# 07_WIFI.net
KiCad netlist of a schematic drawn in Altium Designer
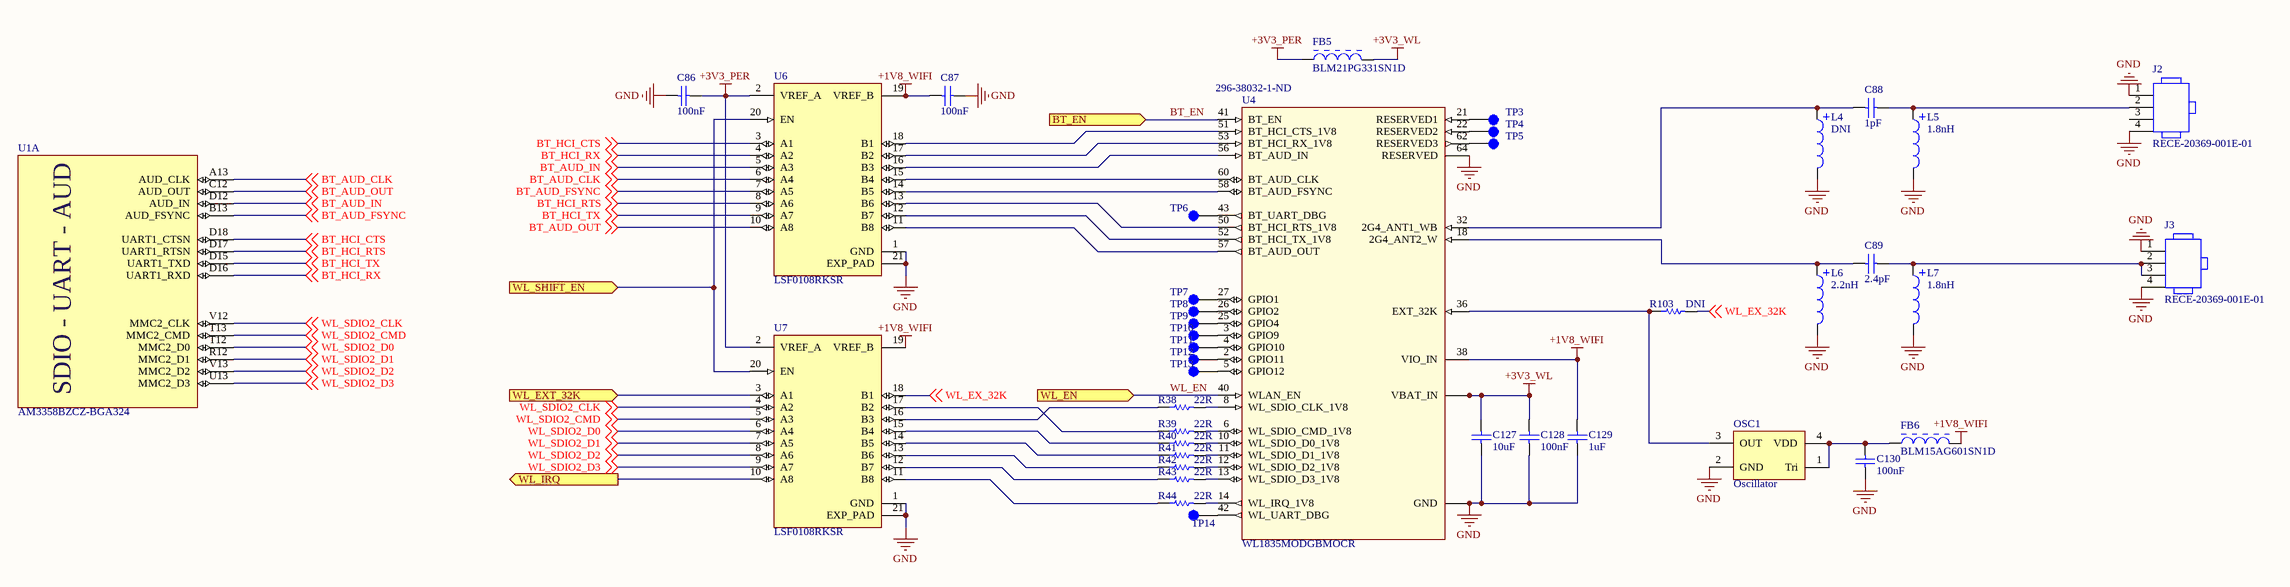
[diagram p0: 07. WIFI.SchDoc]

(export (version "E")
  (design (tool "Eeschema 10.0.6"))
  (components
    (comp (ref "C86")
      (value "100nF")
      (footprint "CAPC1005X60X30LL05T10")
      (description "Chip Capacitor, 0.1 uF, +/- 10%, 16 V, -55 to 125 degC, 0402 (1005 Metric), RoHS, Tape and Reel")
      (fields (field (name "VOLTAGE") "16V") (field (name "TOLERANCE") "10%"))
      (libsource (lib "AM3358_DEV_BOARD") (part "CAP-NP-2"))
    )
    (comp (ref "C87")
      (value "100nF")
      (footprint "CAPC1005X60X30LL05T10")
      (description "Chip Capacitor, 0.1 uF, +/- 10%, 16 V, -55 to 125 degC, 0402 (1005 Metric), RoHS, Tape and Reel")
      (fields (field (name "VOLTAGE") "16V") (field (name "TOLERANCE") "10%"))
      (libsource (lib "AM3358_DEV_BOARD") (part "CAP-NP-2"))
    )
    (comp (ref "C88")
      (value "1pF")
      (footprint "CAPC1005X60X30LL05T10")
      (description "Ceramic; Cap 1 pF; Tol 0.25 pF; Vol-Rtg 50 VDC; SMT; 0402; C0G; Tape & Reel")
      (fields
        (field (name "PART NUMBER") "04025A1R0CAT2A")
        (field (name "MANUFACTURER") "AVX Interconnect / Elco")
      )
      (libsource (lib "AM3358_DEV_BOARD") (part "CAP"))
    )
    (comp (ref "C89")
      (value "2.4pF")
      (footprint "CAPC1005X60X30LL05T10")
      (description "CAP 2.4pF 16V ±0.25pF 01005 (0402 Metric) Thickness 0.22mm SMD")
      (fields (field (name "TOLERANCE") "Â±0.25pF"))
      (libsource (lib "AM3358_DEV_BOARD") (part "CAP"))
    )
    (comp (ref "C127")
      (value "10uF")
      (footprint "CAPC1608X90X35ML10T15")
      (description "Chip Capacitor, 10 uF, +/- 10%, 6.3 V, -55 to 125 degC, 0603 (1608 Metric), RoHS, Tape and Reel")
      (fields (field (name "PART NUMBER") "GRM188R60J106ME47D") (field (name "MANUFACTURER") "Murata"))
      (libsource (lib "Altium Content Vault") (part "CAP"))
    )
    (comp (ref "C128")
      (value "100nF")
      (footprint "CAPC1005X60X30LL05T10")
      (description "Chip Capacitor, 0.1 uF, +/- 10%, 16 V, -55 to 125 degC, 0402 (1005 Metric), RoHS, Tape and Reel")
      (fields (field (name "VOLTAGE") "16V") (field (name "TOLERANCE") "10%"))
      (libsource (lib "AM3358_DEV_BOARD") (part "CAP-NP-2"))
    )
    (comp (ref "C129")
      (value "1uF")
      (footprint "CAPC0402(1005)60_M")
      (description "CAP 1uF 6.3V ±10% 0402 (1005 Metric) Thickness 0.6mm SMD")
      (fields (field (name "TOLERANCE") "Â±10%"))
      (libsource (lib "Altium Content Vault") (part "CAP"))
    )
    (comp (ref "C130")
      (value "100nF")
      (footprint "CAPC1005X60X30LL05T10")
      (description "Chip Capacitor, 0.1 uF, +/- 10%, 16 V, -55 to 125 degC, 0402 (1005 Metric), RoHS, Tape and Reel")
      (fields (field (name "VOLTAGE") "16V") (field (name "TOLERANCE") "10%"))
      (libsource (lib "AM3358_DEV_BOARD") (part "CAP-NP-2"))
    )
    (comp (ref "FB5")
      (value "BLM21PG331SN1D")
      (footprint "MURA-BLM21-H1-CHIP-2_V")
      (fields (field (name "MANUFACTURER") "Murata"))
      (libsource (lib "Altium Content Vault") (part "MURA-FB-2"))
    )
    (comp (ref "FB6")
      (value "BLM15AG601SN1D")
      (footprint "MURA-BLM15-CHIP-2_V")
      (fields (field (name "MANUFACTURER") "Murata"))
      (libsource (lib "Altium Content Vault") (part "MURA-FB-2"))
    )
    (comp (ref "J2")
      (value "RECE-20369-001E-01")
      (footprint "TG-RECE-20369-001E-4_V")
      (description "RF Connector, Onboard Receptacle, IPEX MHFIII")
      (fields (field (name "MANUFACTURER") "Taoglas"))
      (libsource (lib "Altium Content Vault") (part "TG-RECE-20369-001E-01-4"))
    )
    (comp (ref "J3")
      (value "RECE-20369-001E-01")
      (footprint "TG-RECE-20369-001E-4_V")
      (description "RF Connector, Onboard Receptacle, IPEX MHFIII")
      (fields (field (name "MANUFACTURER") "Taoglas"))
      (libsource (lib "Altium Content Vault") (part "TG-RECE-20369-001E-01-4"))
    )
    (comp (ref "L4")
      (value "DNI")
      (footprint "INDC1005X55X25ML5T10")
      (fields (field (name "TOLERANCE") "1%"))
      (libsource (lib "Altium Content Vault") (part "IND_POLAR-2"))
    )
    (comp (ref "L5")
      (value "1.8nH")
      (footprint "INDC1005X55X25ML5T10")
      (fields (field (name "TOLERANCE") "1%"))
      (libsource (lib "Altium Content Vault") (part "IND_POLAR-2"))
    )
    (comp (ref "L6")
      (value "2.2nH")
      (footprint "INDC1005X55X25ML5T10")
      (fields (field (name "TOLERANCE") "1%"))
      (libsource (lib "Altium Content Vault") (part "IND_POLAR-2"))
    )
    (comp (ref "L7")
      (value "1.8nH")
      (footprint "INDC1005X55X25ML5T10")
      (fields (field (name "TOLERANCE") "1%"))
      (libsource (lib "Altium Content Vault") (part "IND_POLAR-2"))
    )
    (comp (ref "OSC1")
      (value "Oscillator")
      (footprint "FP-NX3225SA-MFG")
      (libsource (lib "SyTungNguyen") (part "Oscillator"))
    )
    (comp (ref "R38")
      (value "22R")
      (footprint "RESC1005X40X25LL05T05")
      (description "Chip Resistor, 22 Ohm, +/- 1%, 0.1 W, -55 to 155 degC, 0402 (1005 Metric), RoHS, Tape and Reel")
      (fields (field (name "PARTNUMBER") "ERJ-2RKF22R0X") (field (name "TOLERANCE") "1%"))
      (libsource (lib "AM3358_DEV_BOARD") (part "RES-2"))
    )
    (comp (ref "R39")
      (value "22R")
      (footprint "RESC1005X40X25LL05T05")
      (description "Chip Resistor, 22 Ohm, +/- 1%, 0.1 W, -55 to 155 degC, 0402 (1005 Metric), RoHS, Tape and Reel")
      (fields (field (name "PARTNUMBER") "ERJ-2RKF22R0X") (field (name "TOLERANCE") "1%"))
      (libsource (lib "AM3358_DEV_BOARD") (part "RES-2"))
    )
    (comp (ref "R40")
      (value "22R")
      (footprint "RESC1005X40X25LL05T05")
      (description "Chip Resistor, 22 Ohm, +/- 1%, 0.1 W, -55 to 155 degC, 0402 (1005 Metric), RoHS, Tape and Reel")
      (fields (field (name "PARTNUMBER") "ERJ-2RKF22R0X") (field (name "TOLERANCE") "1%"))
      (libsource (lib "AM3358_DEV_BOARD") (part "RES-2"))
    )
    (comp (ref "R41")
      (value "22R")
      (footprint "RESC1005X40X25LL05T05")
      (description "Chip Resistor, 22 Ohm, +/- 1%, 0.1 W, -55 to 155 degC, 0402 (1005 Metric), RoHS, Tape and Reel")
      (fields (field (name "PARTNUMBER") "ERJ-2RKF22R0X") (field (name "TOLERANCE") "1%"))
      (libsource (lib "AM3358_DEV_BOARD") (part "RES-2"))
    )
    (comp (ref "R42")
      (value "22R")
      (footprint "RESC1005X40X25LL05T05")
      (description "Chip Resistor, 22 Ohm, +/- 1%, 0.1 W, -55 to 155 degC, 0402 (1005 Metric), RoHS, Tape and Reel")
      (fields (field (name "PARTNUMBER") "ERJ-2RKF22R0X") (field (name "TOLERANCE") "1%"))
      (libsource (lib "AM3358_DEV_BOARD") (part "RES-2"))
    )
    (comp (ref "R43")
      (value "22R")
      (footprint "RESC1005X40X25LL05T05")
      (description "Chip Resistor, 22 Ohm, +/- 1%, 0.1 W, -55 to 155 degC, 0402 (1005 Metric), RoHS, Tape and Reel")
      (fields (field (name "PARTNUMBER") "ERJ-2RKF22R0X") (field (name "TOLERANCE") "1%"))
      (libsource (lib "AM3358_DEV_BOARD") (part "RES-2"))
    )
    (comp (ref "R44")
      (value "22R")
      (footprint "RESC1005X40X25LL05T05")
      (description "Chip Resistor, 22 Ohm, +/- 1%, 0.1 W, -55 to 155 degC, 0402 (1005 Metric), RoHS, Tape and Reel")
      (fields (field (name "PARTNUMBER") "ERJ-2RKF22R0X") (field (name "TOLERANCE") "1%"))
      (libsource (lib "AM3358_DEV_BOARD") (part "RES-2"))
    )
    (comp (ref "R103")
      (value "DNI")
      (footprint "RESC1005X40X25LL05T05")
      (description "Chip Resistor, 22 Ohm, +/- 1%, 0.1 W, -55 to 155 degC, 0402 (1005 Metric), RoHS, Tape and Reel")
      (fields (field (name "PARTNUMBER") "ERJ-2RKF22R0X") (field (name "TOLERANCE") "1%"))
      (libsource (lib "AM3358_DEV_BOARD") (part "RES-2"))
    )
    (comp (ref "TP3") (value "Test Point") (footprint "TP") (libsource (lib "SyTungNguyen") (part "TP")))
    (comp (ref "TP4") (value "Test Point") (footprint "TP") (libsource (lib "SyTungNguyen") (part "TP")))
    (comp (ref "TP5") (value "Test Point") (footprint "TP") (libsource (lib "SyTungNguyen") (part "TP")))
    (comp (ref "TP6") (value "Test Point") (footprint "TP") (libsource (lib "SyTungNguyen") (part "TP")))
    (comp (ref "TP7") (value "Test Point") (footprint "TP") (libsource (lib "SyTungNguyen") (part "TP")))
    (comp (ref "TP8") (value "Test Point") (footprint "TP") (libsource (lib "SyTungNguyen") (part "TP")))
    (comp (ref "TP9") (value "Test Point") (footprint "TP") (libsource (lib "SyTungNguyen") (part "TP")))
    (comp (ref "TP10") (value "Test Point") (footprint "TP") (libsource (lib "SyTungNguyen") (part "TP")))
    (comp (ref "TP11") (value "Test Point") (footprint "TP") (libsource (lib "SyTungNguyen") (part "TP")))
    (comp (ref "TP12") (value "Test Point") (footprint "TP") (libsource (lib "SyTungNguyen") (part "TP")))
    (comp (ref "TP13") (value "Test Point") (footprint "TP") (libsource (lib "SyTungNguyen") (part "TP")))
    (comp (ref "TP14") (value "Test Point") (footprint "TP") (libsource (lib "SyTungNguyen") (part "TP")))
    (comp (ref "U1")
      (value "AM3358BZCZ-BGA324")
      (footprint "TI-ZCZ324")
      (libsource (lib "SyTungNguyen") (part "AM3358BZCZ100"))
    )
    (comp (ref "U4")
      (value "WL1835MODGBMOCR")
      (footprint "WL1835MODGBMOCR")
      (description "Bluetooth, WiFi 802.11b/g/n, Bluetooth 4.2 Transceiver Module 2.4GHz Surface Mount")
      (fields (field (name "SUPPLIER PART NUMBER 1") "296-38032-1-ND"))
      (libsource (lib "AM3358_DEV_BOARD") (part "WL1835MOD"))
    )
    (comp (ref "U6")
      (value "LSF0108RKSR")
      (footprint "QFN50P450X250X100-21N")
      (description "Voltage Level Translator Bidirectional 1 Circuit 8 Channel 20-VQFN _4.5x2.5_")
      (fields (field (name "MF") "Texas Instruments"))
      (libsource (lib "SyTungNguyen") (part "LSF0108"))
    )
    (comp (ref "U7")
      (value "LSF0108RKSR")
      (footprint "QFN50P450X250X100-21N")
      (description "Voltage Level Translator Bidirectional 1 Circuit 8 Channel 20-VQFN _4.5x2.5_")
      (fields (field (name "MF") "Texas Instruments"))
      (libsource (lib "SyTungNguyen") (part "LSF0108"))
    )
  )
  (nets
    (net (code "1") (name "+1V8_WIFI") (class "Default")
      (node (ref "C129") (pin "1") (pinfunction "1_1") (pintype "passive"))
      (node (ref "C87") (pin "2") (pinfunction "2_2") (pintype "passive"))
      (node (ref "FB6") (pin "2") (pinfunction "2_2") (pintype "passive"))
      (node (ref "U4") (pin "38") (pinfunction "VIO_IN_38") (pintype "power_in"))
      (node (ref "U6") (pin "19") (pinfunction "VREF_B_19") (pintype "power_in"))
      (node (ref "U7") (pin "19") (pinfunction "VREF_B_19") (pintype "power_in"))
    )
    (net (code "2") (name "+3V3_PER") (class "Default")
      (node (ref "C86") (pin "2") (pinfunction "2_2") (pintype "passive"))
      (node (ref "FB5") (pin "1") (pinfunction "1_1") (pintype "passive"))
      (node (ref "U6") (pin "2") (pinfunction "VREF_A_2") (pintype "power_in"))
      (node (ref "U7") (pin "2") (pinfunction "VREF_A_2") (pintype "power_in"))
    )
    (net (code "3") (name "+3V3_WL") (class "Default")
      (node (ref "C127") (pin "2") (pinfunction "2_2") (pintype "passive"))
      (node (ref "C128") (pin "2") (pinfunction "2_2") (pintype "passive"))
      (node (ref "FB5") (pin "2") (pinfunction "2_2") (pintype "passive"))
      (node (ref "U4") (pin "46") (pinfunction "VBAT_IN_46") (pintype "power_in"))
      (node (ref "U4") (pin "47") (pinfunction "VBAT_IN_47") (pintype "power_in"))
    )
    (net (code "4") (name "/BT_EN") (class "Default")
      (node (ref "U4") (pin "41") (pinfunction "BT_EN_41") (pintype "input"))
    )
    (net (code "5") (name "/WL_EN") (class "Default")
      (node (ref "U4") (pin "40") (pinfunction "WLAN_EN_40") (pintype "input"))
    )
    (net (code "6") (name "/WL_EXT_32K") (class "Default")
      (node (ref "U7") (pin "3") (pinfunction "A1_3") (pintype "bidirectional"))
    )
    (net (code "7") (name "/WL_IRQ") (class "Default")
      (node (ref "U7") (pin "10") (pinfunction "A8_10") (pintype "bidirectional"))
    )
    (net (code "8") (name "/WL_SHIFT_EN") (class "Default")
      (node (ref "U6") (pin "20") (pinfunction "EN_20") (pintype "input"))
      (node (ref "U7") (pin "20") (pinfunction "EN_20") (pintype "input"))
    )
    (net (code "9") (name "BT_AUD_CLK") (class "Default")
      (node (ref "U1") (pin "A13") (pinfunction "AUD_CLK_A13") (pintype "bidirectional"))
      (node (ref "U6") (pin "6") (pinfunction "A4_6") (pintype "bidirectional"))
    )
    (net (code "10") (name "BT_AUD_FSYNC") (class "Default")
      (node (ref "U1") (pin "B13") (pinfunction "AUD_FSYNC_B13") (pintype "bidirectional"))
      (node (ref "U6") (pin "7") (pinfunction "A5_7") (pintype "bidirectional"))
    )
    (net (code "11") (name "BT_AUD_IN") (class "Default")
      (node (ref "U1") (pin "D12") (pinfunction "AUD_IN_D12") (pintype "bidirectional"))
      (node (ref "U6") (pin "5") (pinfunction "A3_5") (pintype "bidirectional"))
    )
    (net (code "12") (name "BT_AUD_OUT") (class "Default")
      (node (ref "U1") (pin "C12") (pinfunction "AUD_OUT_C12") (pintype "bidirectional"))
      (node (ref "U6") (pin "10") (pinfunction "A8_10") (pintype "bidirectional"))
    )
    (net (code "13") (name "BT_HCI_CTS") (class "Default")
      (node (ref "U1") (pin "D18") (pinfunction "UART1_CTSN_D18") (pintype "bidirectional"))
      (node (ref "U6") (pin "3") (pinfunction "A1_3") (pintype "bidirectional"))
    )
    (net (code "14") (name "BT_HCI_RTS") (class "Default")
      (node (ref "U1") (pin "D17") (pinfunction "UART1_RTSN_D17") (pintype "bidirectional"))
      (node (ref "U6") (pin "8") (pinfunction "A6_8") (pintype "bidirectional"))
    )
    (net (code "15") (name "BT_HCI_RX") (class "Default")
      (node (ref "U1") (pin "D16") (pinfunction "UART1_RXD_D16") (pintype "bidirectional"))
      (node (ref "U6") (pin "4") (pinfunction "A2_4") (pintype "bidirectional"))
    )
    (net (code "16") (name "BT_HCI_TX") (class "Default")
      (node (ref "U1") (pin "D15") (pinfunction "UART1_TXD_D15") (pintype "bidirectional"))
      (node (ref "U6") (pin "9") (pinfunction "A7_9") (pintype "bidirectional"))
    )
    (net (code "17") (name "GND") (class "Default")
      (node (ref "C127") (pin "1") (pinfunction "1_1") (pintype "passive"))
      (node (ref "C128") (pin "1") (pinfunction "1_1") (pintype "passive"))
      (node (ref "C129") (pin "2") (pinfunction "2_2") (pintype "passive"))
      (node (ref "C130") (pin "1") (pinfunction "1_1") (pintype "passive"))
      (node (ref "C86") (pin "1") (pinfunction "1_1") (pintype "passive"))
      (node (ref "C87") (pin "1") (pinfunction "1_1") (pintype "passive"))
      (node (ref "J2") (pin "1") (pinfunction "1_1") (pintype "passive"))
      (node (ref "J2") (pin "4") (pinfunction "4_4") (pintype "passive"))
      (node (ref "J3") (pin "1") (pinfunction "1_1") (pintype "passive"))
      (node (ref "J3") (pin "4") (pinfunction "4_4") (pintype "passive"))
      (node (ref "L4") (pin "2") (pinfunction "2_2") (pintype "passive"))
      (node (ref "L5") (pin "2") (pinfunction "2_2") (pintype "passive"))
      (node (ref "L6") (pin "2") (pinfunction "2_2") (pintype "passive"))
      (node (ref "L7") (pin "2") (pinfunction "2_2") (pintype "passive"))
      (node (ref "OSC1") (pin "2") (pinfunction "GND_2") (pintype "passive"))
      (node (ref "U4") (pin "1") (pinfunction "GND_1") (pintype "passive"))
      (node (ref "U4") (pin "15") (pinfunction "GND_15") (pintype "passive"))
      (node (ref "U4") (pin "16") (pinfunction "GND_16") (pintype "passive"))
      (node (ref "U4") (pin "17") (pinfunction "GND_17") (pintype "passive"))
      (node (ref "U4") (pin "19") (pinfunction "GND_19") (pintype "passive"))
      (node (ref "U4") (pin "20") (pinfunction "GND_20") (pintype "passive"))
      (node (ref "U4") (pin "23") (pinfunction "GND_23") (pintype "passive"))
      (node (ref "U4") (pin "24") (pinfunction "GND_24") (pintype "passive"))
      (node (ref "U4") (pin "28") (pinfunction "GND_28") (pintype "passive"))
      (node (ref "U4") (pin "29") (pinfunction "GND_29") (pintype "passive"))
      (node (ref "U4") (pin "30") (pinfunction "GND_30") (pintype "passive"))
      (node (ref "U4") (pin "31") (pinfunction "GND_31") (pintype "passive"))
      (node (ref "U4") (pin "33") (pinfunction "GND_33") (pintype "passive"))
      (node (ref "U4") (pin "34") (pinfunction "GND_34") (pintype "passive"))
      (node (ref "U4") (pin "35") (pinfunction "GND_35") (pintype "passive"))
      (node (ref "U4") (pin "37") (pinfunction "GND_37") (pintype "passive"))
      (node (ref "U4") (pin "39") (pinfunction "GND_39") (pintype "passive"))
      (node (ref "U4") (pin "44") (pinfunction "GND_44") (pintype "passive"))
      (node (ref "U4") (pin "45") (pinfunction "GND_45") (pintype "passive"))
      (node (ref "U4") (pin "48") (pinfunction "GND_48") (pintype "passive"))
      (node (ref "U4") (pin "49") (pinfunction "GND_49") (pintype "passive"))
      (node (ref "U4") (pin "54") (pinfunction "GND_54") (pintype "passive"))
      (node (ref "U4") (pin "55") (pinfunction "GND_55") (pintype "passive"))
      (node (ref "U4") (pin "59") (pinfunction "GND_59") (pintype "passive"))
      (node (ref "U4") (pin "61") (pinfunction "GND_61") (pintype "passive"))
      (node (ref "U4") (pin "63") (pinfunction "GND_63") (pintype "passive"))
      (node (ref "U4") (pin "64") (pinfunction "RESERVED_64") (pintype "passive"))
      (node (ref "U4") (pin "7") (pinfunction "GND_7") (pintype "passive"))
      (node (ref "U4") (pin "9") (pinfunction "GND_9") (pintype "passive"))
      (node (ref "U4") (pin "G1") (pinfunction "GND_G1") (pintype "passive"))
      (node (ref "U4") (pin "G10") (pinfunction "GND_G10") (pintype "passive"))
      (node (ref "U4") (pin "G11") (pinfunction "GND_G11") (pintype "passive"))
      (node (ref "U4") (pin "G12") (pinfunction "GND_G12") (pintype "passive"))
      (node (ref "U4") (pin "G13") (pinfunction "GND_G13") (pintype "passive"))
      (node (ref "U4") (pin "G14") (pinfunction "GND_G14") (pintype "passive"))
      (node (ref "U4") (pin "G15") (pinfunction "GND_G15") (pintype "passive"))
      (node (ref "U4") (pin "G16") (pinfunction "GND_G16") (pintype "passive"))
      (node (ref "U4") (pin "G17") (pinfunction "GND_G17") (pintype "passive"))
      (node (ref "U4") (pin "G18") (pinfunction "GND_G18") (pintype "passive"))
      (node (ref "U4") (pin "G19") (pinfunction "GND_G19") (pintype "passive"))
      (node (ref "U4") (pin "G2") (pinfunction "GND_G2") (pintype "passive"))
      (node (ref "U4") (pin "G20") (pinfunction "GND_G20") (pintype "passive"))
      (node (ref "U4") (pin "G21") (pinfunction "GND_G21") (pintype "passive"))
      (node (ref "U4") (pin "G22") (pinfunction "GND_G22") (pintype "passive"))
      (node (ref "U4") (pin "G23") (pinfunction "GND_G23") (pintype "passive"))
      (node (ref "U4") (pin "G24") (pinfunction "GND_G24") (pintype "passive"))
      (node (ref "U4") (pin "G25") (pinfunction "GND_G25") (pintype "passive"))
      (node (ref "U4") (pin "G26") (pinfunction "GND_G26") (pintype "passive"))
      (node (ref "U4") (pin "G27") (pinfunction "GND_G27") (pintype "passive"))
      (node (ref "U4") (pin "G28") (pinfunction "GND_G28") (pintype "passive"))
      (node (ref "U4") (pin "G29") (pinfunction "GND_G29") (pintype "passive"))
      (node (ref "U4") (pin "G3") (pinfunction "GND_G3") (pintype "passive"))
      (node (ref "U4") (pin "G30") (pinfunction "GND_G30") (pintype "passive"))
      (node (ref "U4") (pin "G31") (pinfunction "GND_G31") (pintype "passive"))
      (node (ref "U4") (pin "G32") (pinfunction "GND_G32") (pintype "passive"))
      (node (ref "U4") (pin "G33") (pinfunction "GND_G33") (pintype "passive"))
      (node (ref "U4") (pin "G34") (pinfunction "GND_G34") (pintype "passive"))
      (node (ref "U4") (pin "G35") (pinfunction "GND_G35") (pintype "passive"))
      (node (ref "U4") (pin "G36") (pinfunction "GND_G36") (pintype "passive"))
      (node (ref "U4") (pin "G4") (pinfunction "GND_G4") (pintype "passive"))
      (node (ref "U4") (pin "G5") (pinfunction "GND_G5") (pintype "passive"))
      (node (ref "U4") (pin "G6") (pinfunction "GND_G6") (pintype "passive"))
      (node (ref "U4") (pin "G7") (pinfunction "GND_G7") (pintype "passive"))
      (node (ref "U4") (pin "G8") (pinfunction "GND_G8") (pintype "passive"))
      (node (ref "U4") (pin "G9") (pinfunction "GND_G9") (pintype "passive"))
      (node (ref "U6") (pin "1") (pinfunction "GND_1") (pintype "power_in"))
      (node (ref "U6") (pin "21") (pinfunction "EXP_PAD_21") (pintype "power_in"))
      (node (ref "U7") (pin "1") (pinfunction "GND_1") (pintype "power_in"))
      (node (ref "U7") (pin "21") (pinfunction "EXP_PAD_21") (pintype "power_in"))
    )
    (net (code "18") (name "Net-(C88-Pad2)") (class "Default")
      (node (ref "C88") (pin "2") (pinfunction "2_2") (pintype "passive"))
      (node (ref "J2") (pin "2") (pinfunction "2_2") (pintype "passive"))
      (node (ref "L5") (pin "1") (pinfunction "1_1") (pintype "passive"))
    )
    (net (code "19") (name "Net-(C89-Pad2)") (class "Default")
      (node (ref "C89") (pin "2") (pinfunction "2_2") (pintype "passive"))
      (node (ref "J3") (pin "2") (pinfunction "2_2") (pintype "passive"))
      (node (ref "J3") (pin "3") (pinfunction "3_3") (pintype "passive"))
      (node (ref "L7") (pin "1") (pinfunction "1_1") (pintype "passive"))
    )
    (net (code "20") (name "Net-(OSC1-OUT)") (class "Default")
      (node (ref "OSC1") (pin "3") (pinfunction "OUT_3") (pintype "passive"))
      (node (ref "R103") (pin "1") (pinfunction "1_1") (pintype "passive"))
      (node (ref "U4") (pin "36") (pinfunction "EXT_32K_36") (pintype "input"))
    )
    (net (code "21") (name "Net-(OSC1-Tri)") (class "Default")
      (node (ref "C130") (pin "2") (pinfunction "2_2") (pintype "passive"))
      (node (ref "FB6") (pin "1") (pinfunction "1_1") (pintype "passive"))
      (node (ref "OSC1") (pin "1") (pinfunction "Tri_1") (pintype "passive"))
      (node (ref "OSC1") (pin "4") (pinfunction "VDD_4") (pintype "passive"))
    )
    (net (code "22") (name "Net-(U4-2G4_ANT1_WB)") (class "Default")
      (node (ref "C88") (pin "1") (pinfunction "1_1") (pintype "passive"))
      (node (ref "L4") (pin "1") (pinfunction "1_1") (pintype "passive"))
      (node (ref "U4") (pin "32") (pinfunction "2G4_ANT1_WB_32") (pintype "input"))
    )
    (net (code "23") (name "Net-(U4-2G4_ANT2_W)") (class "Default")
      (node (ref "C89") (pin "1") (pinfunction "1_1") (pintype "passive"))
      (node (ref "L6") (pin "1") (pinfunction "1_1") (pintype "passive"))
      (node (ref "U4") (pin "18") (pinfunction "2G4_ANT2_W_18") (pintype "input"))
    )
    (net (code "24") (name "Net-(U4-BT_AUD_CLK)") (class "Default")
      (node (ref "U4") (pin "60") (pinfunction "BT_AUD_CLK_60") (pintype "bidirectional"))
      (node (ref "U6") (pin "15") (pinfunction "B4_15") (pintype "bidirectional"))
    )
    (net (code "25") (name "Net-(U4-BT_AUD_FSYNC)") (class "Default")
      (node (ref "U4") (pin "58") (pinfunction "BT_AUD_FSYNC_58") (pintype "bidirectional"))
      (node (ref "U6") (pin "14") (pinfunction "B5_14") (pintype "bidirectional"))
    )
    (net (code "26") (name "Net-(U4-BT_AUD_IN)") (class "Default")
      (node (ref "U4") (pin "56") (pinfunction "BT_AUD_IN_56") (pintype "input"))
      (node (ref "U6") (pin "16") (pinfunction "B3_16") (pintype "bidirectional"))
    )
    (net (code "27") (name "Net-(U4-BT_AUD_OUT)") (class "Default")
      (node (ref "U4") (pin "57") (pinfunction "BT_AUD_OUT_57") (pintype "output"))
      (node (ref "U6") (pin "11") (pinfunction "B8_11") (pintype "bidirectional"))
    )
    (net (code "28") (name "Net-(U4-BT_HCI_CTS_1V8)") (class "Default")
      (node (ref "U4") (pin "51") (pinfunction "BT_HCI_CTS_1V8_51") (pintype "input"))
      (node (ref "U6") (pin "18") (pinfunction "B1_18") (pintype "bidirectional"))
    )
    (net (code "29") (name "Net-(U4-BT_HCI_RTS_1V8)") (class "Default")
      (node (ref "U4") (pin "50") (pinfunction "BT_HCI_RTS_1V8_50") (pintype "output"))
      (node (ref "U6") (pin "13") (pinfunction "B6_13") (pintype "bidirectional"))
    )
    (net (code "30") (name "Net-(U4-BT_HCI_RX_1V8)") (class "Default")
      (node (ref "U4") (pin "53") (pinfunction "BT_HCI_RX_1V8_53") (pintype "input"))
      (node (ref "U6") (pin "17") (pinfunction "B2_17") (pintype "bidirectional"))
    )
    (net (code "31") (name "Net-(U4-BT_HCI_TX_1V8)") (class "Default")
      (node (ref "U4") (pin "52") (pinfunction "BT_HCI_TX_1V8_52") (pintype "output"))
      (node (ref "U6") (pin "12") (pinfunction "B7_12") (pintype "bidirectional"))
    )
    (net (code "32") (name "Net-(U4-BT_UART_DBG)") (class "Default")
      (node (ref "TP6") (pin "1") (pintype "passive"))
      (node (ref "U4") (pin "43") (pinfunction "BT_UART_DBG_43") (pintype "output"))
    )
    (net (code "33") (name "Net-(U4-GPIO1)") (class "Default")
      (node (ref "TP7") (pin "1") (pintype "passive"))
      (node (ref "U4") (pin "27") (pinfunction "GPIO1_27") (pintype "bidirectional"))
    )
    (net (code "34") (name "Net-(U4-GPIO2)") (class "Default")
      (node (ref "TP8") (pin "1") (pintype "passive"))
      (node (ref "U4") (pin "26") (pinfunction "GPIO2_26") (pintype "bidirectional"))
    )
    (net (code "35") (name "Net-(U4-GPIO4)") (class "Default")
      (node (ref "TP9") (pin "1") (pintype "passive"))
      (node (ref "U4") (pin "25") (pinfunction "GPIO4_25") (pintype "bidirectional"))
    )
    (net (code "36") (name "Net-(U4-GPIO9)") (class "Default")
      (node (ref "TP10") (pin "1") (pintype "passive"))
      (node (ref "U4") (pin "3") (pinfunction "GPIO9_3") (pintype "bidirectional"))
    )
    (net (code "37") (name "Net-(U4-GPIO10)") (class "Default")
      (node (ref "TP11") (pin "1") (pintype "passive"))
      (node (ref "U4") (pin "4") (pinfunction "GPIO10_4") (pintype "bidirectional"))
    )
    (net (code "38") (name "Net-(U4-GPIO11)") (class "Default")
      (node (ref "TP12") (pin "1") (pintype "passive"))
      (node (ref "U4") (pin "2") (pinfunction "GPIO11_2") (pintype "bidirectional"))
    )
    (net (code "39") (name "Net-(U4-GPIO12)") (class "Default")
      (node (ref "TP13") (pin "1") (pintype "passive"))
      (node (ref "U4") (pin "5") (pinfunction "GPIO12_5") (pintype "bidirectional"))
    )
    (net (code "40") (name "Net-(U4-RESERVED1)") (class "Default")
      (node (ref "TP3") (pin "1") (pintype "passive"))
      (node (ref "U4") (pin "21") (pinfunction "RESERVED1_21") (pintype "input"))
    )
    (net (code "41") (name "Net-(U4-RESERVED2)") (class "Default")
      (node (ref "TP4") (pin "1") (pintype "passive"))
      (node (ref "U4") (pin "22") (pinfunction "RESERVED2_22") (pintype "input"))
    )
    (net (code "42") (name "Net-(U4-RESERVED3)") (class "Default")
      (node (ref "TP5") (pin "1") (pintype "passive"))
      (node (ref "U4") (pin "62") (pinfunction "RESERVED3_62") (pintype "output"))
    )
    (net (code "43") (name "Net-(U4-WL_IRQ_1V8)") (class "Default")
      (node (ref "R44") (pin "2") (pinfunction "2_2") (pintype "passive"))
      (node (ref "U4") (pin "14") (pinfunction "WL_IRQ_1V8_14") (pintype "output"))
    )
    (net (code "44") (name "Net-(U4-WL_SDIO_CLK_1V8)") (class "Default")
      (node (ref "R38") (pin "2") (pinfunction "2_2") (pintype "passive"))
      (node (ref "U4") (pin "8") (pinfunction "WL_SDIO_CLK_1V8_8") (pintype "input"))
    )
    (net (code "45") (name "Net-(U4-WL_SDIO_CMD_1V8)") (class "Default")
      (node (ref "R39") (pin "2") (pinfunction "2_2") (pintype "passive"))
      (node (ref "U4") (pin "6") (pinfunction "WL_SDIO_CMD_1V8_6") (pintype "bidirectional"))
    )
    (net (code "46") (name "Net-(U4-WL_SDIO_D0_1V8)") (class "Default")
      (node (ref "R40") (pin "2") (pinfunction "2_2") (pintype "passive"))
      (node (ref "U4") (pin "10") (pinfunction "WL_SDIO_D0_1V8_10") (pintype "bidirectional"))
    )
    (net (code "47") (name "Net-(U4-WL_SDIO_D1_1V8)") (class "Default")
      (node (ref "R41") (pin "2") (pinfunction "2_2") (pintype "passive"))
      (node (ref "U4") (pin "11") (pinfunction "WL_SDIO_D1_1V8_11") (pintype "bidirectional"))
    )
    (net (code "48") (name "Net-(U4-WL_SDIO_D2_1V8)") (class "Default")
      (node (ref "R42") (pin "2") (pinfunction "2_2") (pintype "passive"))
      (node (ref "U4") (pin "12") (pinfunction "WL_SDIO_D2_1V8_12") (pintype "bidirectional"))
    )
    (net (code "49") (name "Net-(U4-WL_SDIO_D3_1V8)") (class "Default")
      (node (ref "R43") (pin "2") (pinfunction "2_2") (pintype "passive"))
      (node (ref "U4") (pin "13") (pinfunction "WL_SDIO_D3_1V8_13") (pintype "bidirectional"))
    )
    (net (code "50") (name "Net-(U4-WL_UART_DBG)") (class "Default")
      (node (ref "TP14") (pin "1") (pintype "passive"))
      (node (ref "U4") (pin "42") (pinfunction "WL_UART_DBG_42") (pintype "output"))
    )
    (net (code "51") (name "Net-(U7-B2)") (class "Default")
      (node (ref "R39") (pin "1") (pinfunction "1_1") (pintype "passive"))
      (node (ref "U7") (pin "17") (pinfunction "B2_17") (pintype "bidirectional"))
    )
    (net (code "52") (name "Net-(U7-B3)") (class "Default")
      (node (ref "R38") (pin "1") (pinfunction "1_1") (pintype "passive"))
      (node (ref "U7") (pin "16") (pinfunction "B3_16") (pintype "bidirectional"))
    )
    (net (code "53") (name "Net-(U7-B4)") (class "Default")
      (node (ref "R40") (pin "1") (pinfunction "1_1") (pintype "passive"))
      (node (ref "U7") (pin "15") (pinfunction "B4_15") (pintype "bidirectional"))
    )
    (net (code "54") (name "Net-(U7-B5)") (class "Default")
      (node (ref "R41") (pin "1") (pinfunction "1_1") (pintype "passive"))
      (node (ref "U7") (pin "14") (pinfunction "B5_14") (pintype "bidirectional"))
    )
    (net (code "55") (name "Net-(U7-B6)") (class "Default")
      (node (ref "R42") (pin "1") (pinfunction "1_1") (pintype "passive"))
      (node (ref "U7") (pin "13") (pinfunction "B6_13") (pintype "bidirectional"))
    )
    (net (code "56") (name "Net-(U7-B7)") (class "Default")
      (node (ref "R43") (pin "1") (pinfunction "1_1") (pintype "passive"))
      (node (ref "U7") (pin "12") (pinfunction "B7_12") (pintype "bidirectional"))
    )
    (net (code "57") (name "Net-(U7-B8)") (class "Default")
      (node (ref "R44") (pin "1") (pinfunction "1_1") (pintype "passive"))
      (node (ref "U7") (pin "11") (pinfunction "B8_11") (pintype "bidirectional"))
    )
    (net (code "58") (name "WL_EX_32K") (class "Default")
      (node (ref "R103") (pin "2") (pinfunction "2_2") (pintype "passive"))
      (node (ref "U7") (pin "18") (pinfunction "B1_18") (pintype "bidirectional"))
    )
    (net (code "59") (name "WL_SDIO2_CLK") (class "Default")
      (node (ref "U1") (pin "V12") (pinfunction "MMC2_CLK_V12") (pintype "bidirectional"))
      (node (ref "U7") (pin "4") (pinfunction "A2_4") (pintype "bidirectional"))
    )
    (net (code "60") (name "WL_SDIO2_CMD") (class "Default")
      (node (ref "U1") (pin "T13") (pinfunction "MMC2_CMD_T13") (pintype "bidirectional"))
      (node (ref "U7") (pin "5") (pinfunction "A3_5") (pintype "bidirectional"))
    )
    (net (code "61") (name "WL_SDIO2_D0") (class "Default")
      (node (ref "U1") (pin "T12") (pinfunction "MMC2_D0_T12") (pintype "bidirectional"))
      (node (ref "U7") (pin "6") (pinfunction "A4_6") (pintype "bidirectional"))
    )
    (net (code "62") (name "WL_SDIO2_D1") (class "Default")
      (node (ref "U1") (pin "R12") (pinfunction "MMC2_D1_R12") (pintype "bidirectional"))
      (node (ref "U7") (pin "7") (pinfunction "A5_7") (pintype "bidirectional"))
    )
    (net (code "63") (name "WL_SDIO2_D2") (class "Default")
      (node (ref "U1") (pin "V13") (pinfunction "MMC2_D2_V13") (pintype "bidirectional"))
      (node (ref "U7") (pin "8") (pinfunction "A6_8") (pintype "bidirectional"))
    )
    (net (code "64") (name "WL_SDIO2_D3") (class "Default")
      (node (ref "U1") (pin "U13") (pinfunction "MMC2_D3_U13") (pintype "bidirectional"))
      (node (ref "U7") (pin "9") (pinfunction "A7_9") (pintype "bidirectional"))
    )
    (net (code "65") (name "unconnected-(J2-Pad3)") (class "Default")
      (node (ref "J2") (pin "3") (pinfunction "3_3") (pintype "passive"))
    )
  )
)
